# x3399.net
KiCad netlist of a schematic drawn in Altium Designer
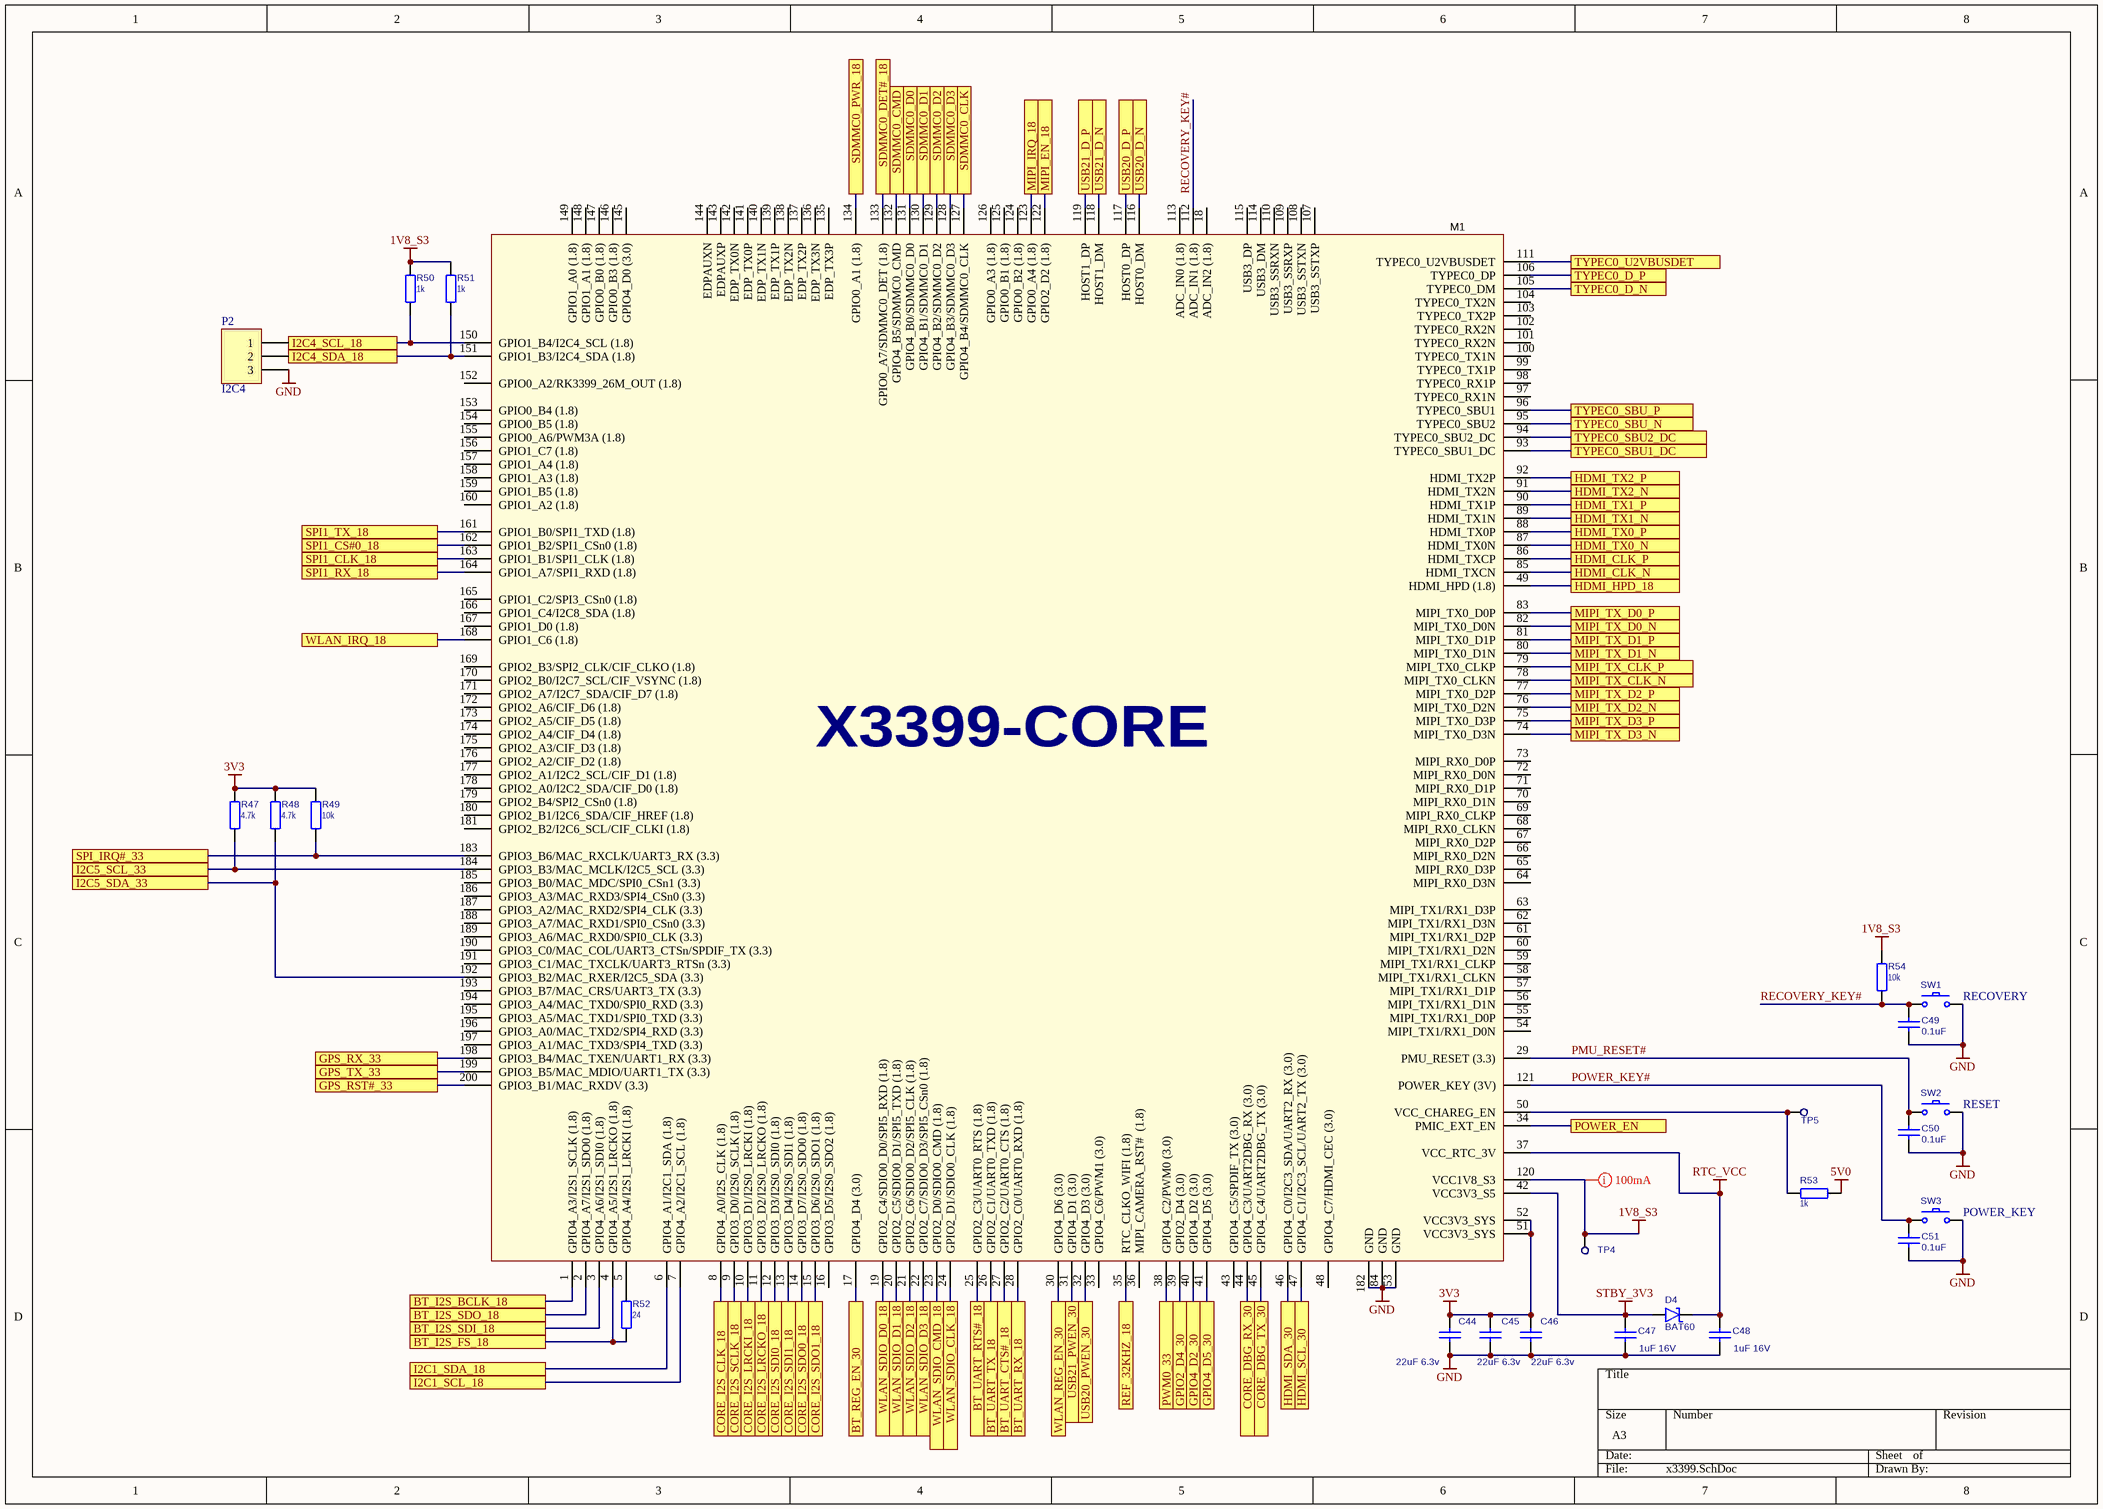
[diagram p0: x3399.SchDoc]

(export (version "E")
  (design (tool "Eeschema 10.0.6"))
  (components
    (comp (ref "C44")
      (value "22uF 6.3v")
      (footprint "C0805")
      (description "CAP_NPOL")
      (fields (field (name "Comment") "CL21A226MQQNNNE"))
      (libsource (lib "capacitors") (part "CAP_NPOL"))
    )
    (comp (ref "C45")
      (value "22uF 6.3v")
      (footprint "C0805")
      (description "CAP_NPOL")
      (fields (field (name "Comment") "CL21A226MQQNNNE"))
      (libsource (lib "capacitors") (part "CAP_NPOL"))
    )
    (comp (ref "C46")
      (value "22uF 6.3v")
      (footprint "C0805")
      (description "CAP_NPOL")
      (fields (field (name "Comment") "CL21A226MQQNNNE"))
      (libsource (lib "capacitors") (part "CAP_NPOL"))
    )
    (comp (ref "C47")
      (value "1uF 16V")
      (footprint "Capacitors:C0603")
      (description "CAP_NPOL")
      (fields (field (name "Comment") "GRM188R61H105KAALD"))
      (libsource (lib "capacitors") (part "CAP_NPOL"))
    )
    (comp (ref "C48")
      (value "1uF 16V")
      (footprint "Capacitors:C0603")
      (description "CAP_NPOL")
      (fields (field (name "Comment") "GRM188R61H105KAALD"))
      (libsource (lib "capacitors") (part "CAP_NPOL"))
    )
    (comp (ref "C49")
      (value "0.1uF")
      (footprint "Capacitors:C0603")
      (description "CAP_NPOL")
      (fields (field (name "Comment") "C1608X7R1H104K080AA"))
      (libsource (lib "capacitors") (part "CAP_NPOL"))
    )
    (comp (ref "C50")
      (value "0.1uF")
      (footprint "Capacitors:C0603")
      (description "CAP_NPOL")
      (fields (field (name "Comment") "C1608X7R1H104K080AA"))
      (libsource (lib "capacitors") (part "CAP_NPOL"))
    )
    (comp (ref "C51")
      (value "0.1uF")
      (footprint "Capacitors:C0603")
      (description "CAP_NPOL")
      (fields (field (name "Comment") "C1608X7R1H104K080AA"))
      (libsource (lib "capacitors") (part "CAP_NPOL"))
    )
    (comp (ref "D4")
      (value "BAT60")
      (footprint "SOD-323")
      (description "SHOTTKY")
      (fields (field (name "Comment") "BAT60AE6327HTSA1"))
      (libsource (lib "diodes") (part "SHOTTKY"))
    )
    (comp (ref "M1")
      (value "X3399-CORE")
      (footprint "X3399-CORE")
      (description "RK3399 Six-Core 64-bit")
      (libsource (lib "X3399-CORE") (part "X3399-CORE"))
    )
    (comp (ref "P2")
      (value "I2C4")
      (footprint "PLS-3")
      (description "Header, 3-Pin")
      (fields (field (name "PUBLISHER") "Altium Limited"))
      (libsource (lib "HDR") (part "HDR 3"))
    )
    (comp (ref "R47")
      (value "4.7k")
      (footprint "R0603")
      (description "RES")
      (libsource (lib "resistors") (part "RESISTOR"))
    )
    (comp (ref "R48")
      (value "4.7k")
      (footprint "R0603")
      (description "RES")
      (libsource (lib "resistors") (part "RESISTOR"))
    )
    (comp (ref "R49")
      (value "10k")
      (footprint "R0603")
      (description "RES")
      (libsource (lib "resistors") (part "RESISTOR"))
    )
    (comp (ref "R50")
      (value "1k")
      (footprint "R0603")
      (description "RES")
      (libsource (lib "resistors") (part "RESISTOR"))
    )
    (comp (ref "R51")
      (value "1k")
      (footprint "R0603")
      (description "RES")
      (libsource (lib "resistors") (part "RESISTOR"))
    )
    (comp (ref "R52")
      (value "24")
      (footprint "R0603")
      (description "RES")
      (libsource (lib "resistors") (part "RESISTOR"))
    )
    (comp (ref "R53")
      (value "1k")
      (footprint "R0603")
      (description "RES")
      (libsource (lib "resistors") (part "RESISTOR"))
    )
    (comp (ref "R54")
      (value "10k")
      (footprint "R0603")
      (description "RES")
      (libsource (lib "resistors") (part "RESISTOR"))
    )
    (comp (ref "SW1")
      (value "RECOVERY")
      (footprint "TACTM-34N-F")
      (description "Microswitches, DTSMB-3 series")
      (libsource (lib "SW-TACT-2PIN") (part "SW tact 2-pin"))
    )
    (comp (ref "SW2")
      (value "RESET")
      (footprint "TACTM-34N-F")
      (description "Microswitches, DTSMB-3 series")
      (libsource (lib "SW-TACT-2PIN") (part "SW tact 2-pin"))
    )
    (comp (ref "SW3")
      (value "POWER_KEY")
      (footprint "TACTM-34N-F")
      (description "Microswitches, DTSMB-3 series")
      (libsource (lib "SW-TACT-2PIN") (part "SW tact 2-pin"))
    )
    (comp (ref "TP4")
      (value "TEST-POINT")
      (footprint "PAD")
      (description "PCB terminal block")
      (libsource (lib "TestPoint") (part "TEST-POINT"))
    )
    (comp (ref "TP5")
      (value "TEST-POINT")
      (footprint "PAD")
      (description "PCB terminal block")
      (libsource (lib "TestPoint") (part "TEST-POINT"))
    )
  )
  (nets
    (net (code "1") (name "/BT_I2S_BCLK_18") (class "Default")
      (node (ref "M1") (pin "1") (pinfunction "GPIO4_A3/I2S1_SCLK_(1.8)_1") (pintype "passive"))
    )
    (net (code "2") (name "/BT_I2S_FS_18") (class "Default")
      (node (ref "M1") (pin "4") (pinfunction "GPIO4_A5/I2S1_LRCKO_(1.8)_4") (pintype "passive"))
      (node (ref "R52") (pin "2") (pinfunction "2_2") (pintype "passive"))
    )
    (net (code "3") (name "/BT_I2S_SDI_18") (class "Default")
      (node (ref "M1") (pin "3") (pinfunction "GPIO4_A6/I2S1_SDI0_(1.8)_3") (pintype "passive"))
    )
    (net (code "4") (name "/BT_I2S_SDO_18") (class "Default")
      (node (ref "M1") (pin "2") (pinfunction "GPIO4_A7/I2S1_SDO0_(1.8)_2") (pintype "passive"))
    )
    (net (code "5") (name "/BT_REG_EN_30") (class "Default")
      (node (ref "M1") (pin "17") (pinfunction "GPIO4_D4_(3.0)_17") (pintype "passive"))
    )
    (net (code "6") (name "/BT_UART_CTS#_18") (class "Default")
      (node (ref "M1") (pin "27") (pinfunction "GPIO2_C2/UART0_CTS_(1.8)_27") (pintype "passive"))
    )
    (net (code "7") (name "/BT_UART_RTS#_18") (class "Default")
      (node (ref "M1") (pin "25") (pinfunction "GPIO2_C3/UART0_RTS_(1.8)_25") (pintype "passive"))
    )
    (net (code "8") (name "/BT_UART_RX_18") (class "Default")
      (node (ref "M1") (pin "28") (pinfunction "GPIO2_C0/UART0_RXD_(1.8)_28") (pintype "passive"))
    )
    (net (code "9") (name "/BT_UART_TX_18") (class "Default")
      (node (ref "M1") (pin "26") (pinfunction "GPIO2_C1/UART0_TXD_(1.8)_26") (pintype "passive"))
    )
    (net (code "10") (name "/CORE_DBG_RX_30") (class "Default")
      (node (ref "M1") (pin "44") (pinfunction "GPIO4_C3/UART2DBG_RX_(3.0)_44") (pintype "passive"))
    )
    (net (code "11") (name "/CORE_DBG_TX_30") (class "Default")
      (node (ref "M1") (pin "45") (pinfunction "GPIO4_C4/UART2DBG_TX_(3.0)_45") (pintype "passive"))
    )
    (net (code "12") (name "/CORE_I2S_CLK_18") (class "Default")
      (node (ref "M1") (pin "8") (pinfunction "GPIO4_A0/I2S_CLK_(1.8)_8") (pintype "passive"))
    )
    (net (code "13") (name "/CORE_I2S_LRCKI_18") (class "Default")
      (node (ref "M1") (pin "10") (pinfunction "GPIO3_D1/I2S0_LRCKI_(1.8)_10") (pintype "passive"))
    )
    (net (code "14") (name "/CORE_I2S_LRCKO_18") (class "Default")
      (node (ref "M1") (pin "11") (pinfunction "GPIO3_D2/I2S0_LRCKO_(1.8)_11") (pintype "passive"))
    )
    (net (code "15") (name "/CORE_I2S_SCLK_18") (class "Default")
      (node (ref "M1") (pin "9") (pinfunction "GPIO3_D0/I2S0_SCLK_(1.8)_9") (pintype "passive"))
    )
    (net (code "16") (name "/CORE_I2S_SDI0_18") (class "Default")
      (node (ref "M1") (pin "12") (pinfunction "GPIO3_D3/I2S0_SDI0_(1.8)_12") (pintype "passive"))
    )
    (net (code "17") (name "/CORE_I2S_SDI1_18") (class "Default")
      (node (ref "M1") (pin "13") (pinfunction "GPIO3_D4/I2S0_SDI1_(1.8)_13") (pintype "passive"))
    )
    (net (code "18") (name "/CORE_I2S_SDO0_18") (class "Default")
      (node (ref "M1") (pin "14") (pinfunction "GPIO3_D7/I2S0_SDO0_(1.8)_14") (pintype "passive"))
    )
    (net (code "19") (name "/CORE_I2S_SDO1_18") (class "Default")
      (node (ref "M1") (pin "15") (pinfunction "GPIO3_D6/I2S0_SDO1_(1.8)_15") (pintype "passive"))
    )
    (net (code "20") (name "/GPIO2_D4_30") (class "Default")
      (node (ref "M1") (pin "39") (pinfunction "GPIO2_D4_(3.0)_39") (pintype "passive"))
    )
    (net (code "21") (name "/GPIO4_D2_30") (class "Default")
      (node (ref "M1") (pin "40") (pinfunction "GPIO4_D2_(3.0)_40") (pintype "passive"))
    )
    (net (code "22") (name "/GPIO4_D5_30") (class "Default")
      (node (ref "M1") (pin "41") (pinfunction "GPIO4_D5_(3.0)_41") (pintype "passive"))
    )
    (net (code "23") (name "/GPS_RST#_33") (class "Default")
      (node (ref "M1") (pin "200") (pinfunction "GPIO3_B1/MAC_RXDV_(3.3)_200") (pintype "passive"))
    )
    (net (code "24") (name "/GPS_RX_33") (class "Default")
      (node (ref "M1") (pin "198") (pinfunction "GPIO3_B4/MAC_TXEN/UART1_RX_(3.3)_198") (pintype "passive"))
    )
    (net (code "25") (name "/GPS_TX_33") (class "Default")
      (node (ref "M1") (pin "199") (pinfunction "GPIO3_B5/MAC_MDIO/UART1_TX_(3.3)_199") (pintype "passive"))
    )
    (net (code "26") (name "/HDMI_CLK_N") (class "Default")
      (node (ref "M1") (pin "85") (pinfunction "HDMI_TXCN_85") (pintype "passive"))
    )
    (net (code "27") (name "/HDMI_CLK_P") (class "Default")
      (node (ref "M1") (pin "86") (pinfunction "HDMI_TXCP_86") (pintype "passive"))
    )
    (net (code "28") (name "/HDMI_HPD_18") (class "Default")
      (node (ref "M1") (pin "49") (pinfunction "HDMI_HPD_(1.8)_49") (pintype "passive"))
    )
    (net (code "29") (name "/HDMI_SCL_30") (class "Default")
      (node (ref "M1") (pin "47") (pinfunction "GPIO4_C1/I2C3_SCL/UART2_TX_(3.0)_47") (pintype "passive"))
    )
    (net (code "30") (name "/HDMI_SDA_30") (class "Default")
      (node (ref "M1") (pin "46") (pinfunction "GPIO4_C0/I2C3_SDA/UART2_RX_(3.0)_46") (pintype "passive"))
    )
    (net (code "31") (name "/HDMI_TX0_N") (class "Default")
      (node (ref "M1") (pin "87") (pinfunction "HDMI_TX0N_87") (pintype "passive"))
    )
    (net (code "32") (name "/HDMI_TX0_P") (class "Default")
      (node (ref "M1") (pin "88") (pinfunction "HDMI_TX0P_88") (pintype "passive"))
    )
    (net (code "33") (name "/HDMI_TX1_N") (class "Default")
      (node (ref "M1") (pin "89") (pinfunction "HDMI_TX1N_89") (pintype "passive"))
    )
    (net (code "34") (name "/HDMI_TX1_P") (class "Default")
      (node (ref "M1") (pin "90") (pinfunction "HDMI_TX1P_90") (pintype "passive"))
    )
    (net (code "35") (name "/HDMI_TX2_N") (class "Default")
      (node (ref "M1") (pin "91") (pinfunction "HDMI_TX2N_91") (pintype "passive"))
    )
    (net (code "36") (name "/HDMI_TX2_P") (class "Default")
      (node (ref "M1") (pin "92") (pinfunction "HDMI_TX2P_92") (pintype "passive"))
    )
    (net (code "37") (name "/I2C1_SCL_18") (class "Default")
      (node (ref "M1") (pin "7") (pinfunction "GPIO4_A2/I2C1_SCL_(1.8)_7") (pintype "passive"))
    )
    (net (code "38") (name "/I2C1_SDA_18") (class "Default")
      (node (ref "M1") (pin "6") (pinfunction "GPIO4_A1/I2C1_SDA_(1.8)_6") (pintype "passive"))
    )
    (net (code "39") (name "/I2C4_SCL_18") (class "Default")
      (node (ref "M1") (pin "150") (pinfunction "GPIO1_B4/I2C4_SCL_(1.8)_150") (pintype "passive"))
      (node (ref "P2") (pin "1") (pinfunction "1_1") (pintype "passive"))
      (node (ref "R50") (pin "1") (pinfunction "1_1") (pintype "passive"))
    )
    (net (code "40") (name "/I2C4_SDA_18") (class "Default")
      (node (ref "M1") (pin "151") (pinfunction "GPIO1_B3/I2C4_SDA_(1.8)_151") (pintype "passive"))
      (node (ref "P2") (pin "2") (pinfunction "2_2") (pintype "passive"))
      (node (ref "R51") (pin "2") (pinfunction "2_2") (pintype "passive"))
    )
    (net (code "41") (name "/I2C5_SCL_33") (class "Default")
      (node (ref "M1") (pin "184") (pinfunction "GPIO3_B3/MAC_MCLK/I2C5_SCL_(3.3)_184") (pintype "passive"))
      (node (ref "R47") (pin "1") (pinfunction "1_1") (pintype "passive"))
    )
    (net (code "42") (name "/I2C5_SDA_33") (class "Default")
      (node (ref "M1") (pin "192") (pinfunction "GPIO3_B2/MAC_RXER/I2C5_SDA_(3.3)_192") (pintype "passive"))
      (node (ref "R48") (pin "2") (pinfunction "2_2") (pintype "passive"))
    )
    (net (code "43") (name "/MIPI_EN_18") (class "Default")
      (node (ref "M1") (pin "122") (pinfunction "GPIO2_D2_(1.8)_122") (pintype "passive"))
    )
    (net (code "44") (name "/MIPI_IRQ_18") (class "Default")
      (node (ref "M1") (pin "123") (pinfunction "GPIO0_A4_(1.8)_123") (pintype "passive"))
    )
    (net (code "45") (name "/MIPI_TX_CLK_N") (class "Default")
      (node (ref "M1") (pin "78") (pinfunction "MIPI_TX0_CLKN_78") (pintype "passive"))
    )
    (net (code "46") (name "/MIPI_TX_CLK_P") (class "Default")
      (node (ref "M1") (pin "79") (pinfunction "MIPI_TX0_CLKP_79") (pintype "passive"))
    )
    (net (code "47") (name "/MIPI_TX_D0_N") (class "Default")
      (node (ref "M1") (pin "82") (pinfunction "MIPI_TX0_D0N_82") (pintype "passive"))
    )
    (net (code "48") (name "/MIPI_TX_D0_P") (class "Default")
      (node (ref "M1") (pin "83") (pinfunction "MIPI_TX0_D0P_83") (pintype "passive"))
    )
    (net (code "49") (name "/MIPI_TX_D1_N") (class "Default")
      (node (ref "M1") (pin "80") (pinfunction "MIPI_TX0_D1N_80") (pintype "passive"))
    )
    (net (code "50") (name "/MIPI_TX_D1_P") (class "Default")
      (node (ref "M1") (pin "81") (pinfunction "MIPI_TX0_D1P_81") (pintype "passive"))
    )
    (net (code "51") (name "/MIPI_TX_D2_N") (class "Default")
      (node (ref "M1") (pin "76") (pinfunction "MIPI_TX0_D2N_76") (pintype "passive"))
    )
    (net (code "52") (name "/MIPI_TX_D2_P") (class "Default")
      (node (ref "M1") (pin "77") (pinfunction "MIPI_TX0_D2P_77") (pintype "passive"))
    )
    (net (code "53") (name "/MIPI_TX_D3_N") (class "Default")
      (node (ref "M1") (pin "74") (pinfunction "MIPI_TX0_D3N_74") (pintype "passive"))
    )
    (net (code "54") (name "/MIPI_TX_D3_P") (class "Default")
      (node (ref "M1") (pin "75") (pinfunction "MIPI_TX0_D3P_75") (pintype "passive"))
    )
    (net (code "55") (name "/PMU_RESET#") (class "Default")
      (node (ref "C50") (pin "1") (pinfunction "1_1") (pintype "passive"))
      (node (ref "M1") (pin "29") (pinfunction "PMU_RESET_(3.3)_29") (pintype "passive"))
      (node (ref "SW2") (pin "1") (pintype "passive"))
    )
    (net (code "56") (name "/POWER_EN") (class "Default")
      (node (ref "M1") (pin "34") (pinfunction "PMIC_EXT_EN_34") (pintype "passive"))
    )
    (net (code "57") (name "/POWER_KEY#") (class "Default")
      (node (ref "C51") (pin "1") (pinfunction "1_1") (pintype "passive"))
      (node (ref "M1") (pin "121") (pinfunction "POWER_KEY_(3V)_121") (pintype "passive"))
      (node (ref "SW3") (pin "1") (pintype "passive"))
    )
    (net (code "58") (name "/PWM0_33") (class "Default")
      (node (ref "M1") (pin "38") (pinfunction "GPIO4_C2/PWM0_(3.0)_38") (pintype "passive"))
    )
    (net (code "59") (name "/RECOVERY_KEY#") (class "Default")
      (node (ref "C49") (pin "1") (pinfunction "1_1") (pintype "passive"))
      (node (ref "M1") (pin "112") (pinfunction "ADC_IN1_(1.8)_112") (pintype "passive"))
      (node (ref "R54") (pin "1") (pinfunction "1_1") (pintype "passive"))
      (node (ref "SW1") (pin "1") (pintype "passive"))
    )
    (net (code "60") (name "/REF_32KHZ_18") (class "Default")
      (node (ref "M1") (pin "35") (pinfunction "RTC_CLKO_WIFI_(1.8)_35") (pintype "passive"))
    )
    (net (code "61") (name "/SDMMC0_CLK") (class "Default")
      (node (ref "M1") (pin "127") (pinfunction "GPIO4_B4/SDMMC0_CLK_127") (pintype "passive"))
    )
    (net (code "62") (name "/SDMMC0_CMD") (class "Default")
      (node (ref "M1") (pin "132") (pinfunction "GPIO4_B5/SDMMC0_CMD_132") (pintype "passive"))
    )
    (net (code "63") (name "/SDMMC0_D0") (class "Default")
      (node (ref "M1") (pin "131") (pinfunction "GPIO4_B0/SDMMC0_D0_131") (pintype "passive"))
    )
    (net (code "64") (name "/SDMMC0_D1") (class "Default")
      (node (ref "M1") (pin "130") (pinfunction "GPIO4_B1/SDMMC0_D1_130") (pintype "passive"))
    )
    (net (code "65") (name "/SDMMC0_D2") (class "Default")
      (node (ref "M1") (pin "129") (pinfunction "GPIO4_B2/SDMMC0_D2_129") (pintype "passive"))
    )
    (net (code "66") (name "/SDMMC0_D3") (class "Default")
      (node (ref "M1") (pin "128") (pinfunction "GPIO4_B3/SDMMC0_D3_128") (pintype "passive"))
    )
    (net (code "67") (name "/SDMMC0_DET#_18") (class "Default")
      (node (ref "M1") (pin "133") (pinfunction "GPIO0_A7/SDMMC0_DET_(1.8)_133") (pintype "passive"))
    )
    (net (code "68") (name "/SDMMC0_PWR_18") (class "Default")
      (node (ref "M1") (pin "134") (pinfunction "GPIO0_A1_(1.8)_134") (pintype "passive"))
    )
    (net (code "69") (name "/SPI1_CLK_18") (class "Default")
      (node (ref "M1") (pin "163") (pinfunction "GPIO1_B1/SPI1_CLK_(1.8)_163") (pintype "passive"))
    )
    (net (code "70") (name "/SPI1_CS#0_18") (class "Default")
      (node (ref "M1") (pin "162") (pinfunction "GPIO1_B2/SPI1_CSn0_(1.8)_162") (pintype "passive"))
    )
    (net (code "71") (name "/SPI1_RX_18") (class "Default")
      (node (ref "M1") (pin "164") (pinfunction "GPIO1_A7/SPI1_RXD_(1.8)_164") (pintype "passive"))
    )
    (net (code "72") (name "/SPI1_TX_18") (class "Default")
      (node (ref "M1") (pin "161") (pinfunction "GPIO1_B0/SPI1_TXD_(1.8)_161") (pintype "passive"))
    )
    (net (code "73") (name "/SPI_IRQ#_33") (class "Default")
      (node (ref "M1") (pin "183") (pinfunction "GPIO3_B6/MAC_RXCLK/UART3_RX_(3.3)_183") (pintype "passive"))
      (node (ref "R49") (pin "2") (pinfunction "2_2") (pintype "passive"))
    )
    (net (code "74") (name "/TYPEC0_D_N") (class "Default")
      (node (ref "M1") (pin "105") (pinfunction "TYPEC0_DM_105") (pintype "passive"))
    )
    (net (code "75") (name "/TYPEC0_D_P") (class "Default")
      (node (ref "M1") (pin "106") (pinfunction "TYPEC0_DP_106") (pintype "passive"))
    )
    (net (code "76") (name "/TYPEC0_SBU1_DC") (class "Default")
      (node (ref "M1") (pin "93") (pinfunction "TYPEC0_SBU1_DC_93") (pintype "passive"))
    )
    (net (code "77") (name "/TYPEC0_SBU2_DC") (class "Default")
      (node (ref "M1") (pin "94") (pinfunction "TYPEC0_SBU2_DC_94") (pintype "passive"))
    )
    (net (code "78") (name "/TYPEC0_SBU_N") (class "Default")
      (node (ref "M1") (pin "95") (pinfunction "TYPEC0_SBU2_95") (pintype "passive"))
    )
    (net (code "79") (name "/TYPEC0_SBU_P") (class "Default")
      (node (ref "M1") (pin "96") (pinfunction "TYPEC0_SBU1_96") (pintype "passive"))
    )
    (net (code "80") (name "/TYPEC0_U2VBUSDET") (class "Default")
      (node (ref "M1") (pin "111") (pinfunction "TYPEC0_U2VBUSDET_111") (pintype "passive"))
    )
    (net (code "81") (name "/USB20_D_N") (class "Default")
      (node (ref "M1") (pin "116") (pinfunction "HOST0_DM_116") (pintype "passive"))
    )
    (net (code "82") (name "/USB20_D_P") (class "Default")
      (node (ref "M1") (pin "117") (pinfunction "HOST0_DP_117") (pintype "passive"))
    )
    (net (code "83") (name "/USB20_PWEN_30") (class "Default")
      (node (ref "M1") (pin "32") (pinfunction "GPIO4_D3_(3.0)_32") (pintype "passive"))
    )
    (net (code "84") (name "/USB21_D_N") (class "Default")
      (node (ref "M1") (pin "118") (pinfunction "HOST1_DM_118") (pintype "passive"))
    )
    (net (code "85") (name "/USB21_D_P") (class "Default")
      (node (ref "M1") (pin "119") (pinfunction "HOST1_DP_119") (pintype "passive"))
    )
    (net (code "86") (name "/USB21_PWEN_30") (class "Default")
      (node (ref "M1") (pin "31") (pinfunction "GPIO4_D1_(3.0)_31") (pintype "passive"))
    )
    (net (code "87") (name "/WLAN_IRQ_18") (class "Default")
      (node (ref "M1") (pin "168") (pinfunction "GPIO1_C6_(1.8)_168") (pintype "passive"))
    )
    (net (code "88") (name "/WLAN_REG_EN_30") (class "Default")
      (node (ref "M1") (pin "30") (pinfunction "GPIO4_D6_(3.0)_30") (pintype "passive"))
    )
    (net (code "89") (name "/WLAN_SDIO_CLK_18") (class "Default")
      (node (ref "M1") (pin "24") (pinfunction "GPIO2_D1/SDIO0_CLK_(1.8)_24") (pintype "passive"))
    )
    (net (code "90") (name "/WLAN_SDIO_CMD_18") (class "Default")
      (node (ref "M1") (pin "23") (pinfunction "GPIO2_D0/SDIO0_CMD_(1.8)_23") (pintype "passive"))
    )
    (net (code "91") (name "/WLAN_SDIO_D0_18") (class "Default")
      (node (ref "M1") (pin "19") (pinfunction "GPIO2_C4/SDIO0_D0/SPI5_RXD_(1.8)_19") (pintype "passive"))
    )
    (net (code "92") (name "/WLAN_SDIO_D1_18") (class "Default")
      (node (ref "M1") (pin "20") (pinfunction "GPIO2_C5/SDIO0_D1/SPI5_TXD_(1.8)_20") (pintype "passive"))
    )
    (net (code "93") (name "/WLAN_SDIO_D2_18") (class "Default")
      (node (ref "M1") (pin "21") (pinfunction "GPIO2_C6/SDIO0_D2/SPI5_CLK_(1.8)_21") (pintype "passive"))
    )
    (net (code "94") (name "/WLAN_SDIO_D3_18") (class "Default")
      (node (ref "M1") (pin "22") (pinfunction "GPIO2_C7/SDIO0_D3/SPI5_CSn0_(1.8)_22") (pintype "passive"))
    )
    (net (code "95") (name "1V8_S3") (class "Default")
      (node (ref "M1") (pin "120") (pinfunction "VCC1V8_S3_120") (pintype "passive"))
      (node (ref "R50") (pin "2") (pinfunction "2_2") (pintype "passive"))
      (node (ref "R51") (pin "1") (pinfunction "1_1") (pintype "passive"))
      (node (ref "R54") (pin "2") (pinfunction "2_2") (pintype "passive"))
      (node (ref "TP4") (pin "1") (pinfunction "1_1") (pintype "passive"))
    )
    (net (code "96") (name "3V3") (class "Default")
      (node (ref "C44") (pin "1") (pinfunction "1_1") (pintype "passive"))
      (node (ref "C45") (pin "1") (pinfunction "1_1") (pintype "passive"))
      (node (ref "C46") (pin "1") (pinfunction "1_1") (pintype "passive"))
      (node (ref "M1") (pin "51") (pinfunction "VCC3V3_SYS_51") (pintype "passive"))
      (node (ref "M1") (pin "52") (pinfunction "VCC3V3_SYS_52") (pintype "passive"))
      (node (ref "R47") (pin "2") (pinfunction "2_2") (pintype "passive"))
      (node (ref "R48") (pin "1") (pinfunction "1_1") (pintype "passive"))
      (node (ref "R49") (pin "1") (pinfunction "1_1") (pintype "passive"))
    )
    (net (code "97") (name "5V0") (class "Default")
      (node (ref "R53") (pin "1") (pinfunction "1_1") (pintype "passive"))
    )
    (net (code "98") (name "GND") (class "Default")
      (node (ref "C44") (pin "2") (pinfunction "2_2") (pintype "passive"))
      (node (ref "C45") (pin "2") (pinfunction "2_2") (pintype "passive"))
      (node (ref "C46") (pin "2") (pinfunction "2_2") (pintype "passive"))
      (node (ref "C47") (pin "1") (pinfunction "1_1") (pintype "passive"))
      (node (ref "C48") (pin "1") (pinfunction "1_1") (pintype "passive"))
      (node (ref "C49") (pin "2") (pinfunction "2_2") (pintype "passive"))
      (node (ref "C50") (pin "2") (pinfunction "2_2") (pintype "passive"))
      (node (ref "C51") (pin "2") (pinfunction "2_2") (pintype "passive"))
      (node (ref "M1") (pin "182") (pinfunction "GND_182") (pintype "passive"))
      (node (ref "M1") (pin "53") (pinfunction "GND_53") (pintype "passive"))
      (node (ref "M1") (pin "84") (pinfunction "GND_84") (pintype "passive"))
      (node (ref "P2") (pin "3") (pinfunction "3_3") (pintype "passive"))
      (node (ref "SW1") (pin "2") (pintype "passive"))
      (node (ref "SW2") (pin "2") (pintype "passive"))
      (node (ref "SW3") (pin "2") (pintype "passive"))
    )
    (net (code "99") (name "Net-(M1-GPIO4_A4{slash}I2S1_LRCKI_(1.8))") (class "Default")
      (node (ref "M1") (pin "5") (pinfunction "GPIO4_A4/I2S1_LRCKI_(1.8)_5") (pintype "passive"))
      (node (ref "R52") (pin "1") (pinfunction "1_1") (pintype "passive"))
    )
    (net (code "100") (name "Net-(M1-VCC_CHAREG_EN)") (class "Default")
      (node (ref "M1") (pin "50") (pinfunction "VCC_CHAREG_EN_50") (pintype "passive"))
      (node (ref "R53") (pin "2") (pinfunction "2_2") (pintype "passive"))
      (node (ref "TP5") (pin "1") (pinfunction "1_1") (pintype "passive"))
    )
    (net (code "101") (name "RTC_VCC") (class "Default")
      (node (ref "C48") (pin "2") (pinfunction "2_2") (pintype "passive"))
      (node (ref "D4") (pin "2") (pinfunction "K_2") (pintype "passive"))
      (node (ref "M1") (pin "37") (pinfunction "VCC_RTC_3V_37") (pintype "passive"))
    )
    (net (code "102") (name "STBY_3V3") (class "Default")
      (node (ref "C47") (pin "2") (pinfunction "2_2") (pintype "passive"))
      (node (ref "D4") (pin "1") (pinfunction "A_1") (pintype "passive"))
      (node (ref "M1") (pin "42") (pinfunction "VCC3V3_S5_42") (pintype "passive"))
    )
    (net (code "103") (name "unconnected-(M1-ADC_IN0_(1.8)-Pad113)") (class "Default")
      (node (ref "M1") (pin "113") (pinfunction "ADC_IN0_(1.8)_113") (pintype "passive"))
    )
    (net (code "104") (name "unconnected-(M1-ADC_IN2_(1.8)-Pad18)") (class "Default")
      (node (ref "M1") (pin "18") (pinfunction "ADC_IN2_(1.8)_18") (pintype "passive"))
    )
    (net (code "105") (name "unconnected-(M1-EDPAUXN-Pad144)") (class "Default")
      (node (ref "M1") (pin "144") (pinfunction "EDPAUXN_144") (pintype "passive"))
    )
    (net (code "106") (name "unconnected-(M1-EDPAUXP-Pad143)") (class "Default")
      (node (ref "M1") (pin "143") (pinfunction "EDPAUXP_143") (pintype "passive"))
    )
    (net (code "107") (name "unconnected-(M1-EDP_TX0N-Pad142)") (class "Default")
      (node (ref "M1") (pin "142") (pinfunction "EDP_TX0N_142") (pintype "passive"))
    )
    (net (code "108") (name "unconnected-(M1-EDP_TX0P-Pad141)") (class "Default")
      (node (ref "M1") (pin "141") (pinfunction "EDP_TX0P_141") (pintype "passive"))
    )
    (net (code "109") (name "unconnected-(M1-EDP_TX1N-Pad140)") (class "Default")
      (node (ref "M1") (pin "140") (pinfunction "EDP_TX1N_140") (pintype "passive"))
    )
    (net (code "110") (name "unconnected-(M1-EDP_TX1P-Pad139)") (class "Default")
      (node (ref "M1") (pin "139") (pinfunction "EDP_TX1P_139") (pintype "passive"))
    )
    (net (code "111") (name "unconnected-(M1-EDP_TX2N-Pad138)") (class "Default")
      (node (ref "M1") (pin "138") (pinfunction "EDP_TX2N_138") (pintype "passive"))
    )
    (net (code "112") (name "unconnected-(M1-EDP_TX2P-Pad137)") (class "Default")
      (node (ref "M1") (pin "137") (pinfunction "EDP_TX2P_137") (pintype "passive"))
    )
    (net (code "113") (name "unconnected-(M1-EDP_TX3N-Pad136)") (class "Default")
      (node (ref "M1") (pin "136") (pinfunction "EDP_TX3N_136") (pintype "passive"))
    )
    (net (code "114") (name "unconnected-(M1-EDP_TX3P-Pad135)") (class "Default")
      (node (ref "M1") (pin "135") (pinfunction "EDP_TX3P_135") (pintype "passive"))
    )
    (net (code "115") (name "unconnected-(M1-GPIO0_A2{slash}RK3399_26M_OUT_(1.8)-Pad152)") (class "Default")
      (node (ref "M1") (pin "152") (pinfunction "GPIO0_A2/RK3399_26M_OUT_(1.8)_152") (pintype "passive"))
    )
    (net (code "116") (name "unconnected-(M1-GPIO0_A3_(1.8)-Pad126)") (class "Default")
      (node (ref "M1") (pin "126") (pinfunction "GPIO0_A3_(1.8)_126") (pintype "passive"))
    )
    (net (code "117") (name "unconnected-(M1-GPIO0_A6{slash}PWM3A_(1.8)-Pad155)") (class "Default")
      (node (ref "M1") (pin "155") (pinfunction "GPIO0_A6/PWM3A_(1.8)_155") (pintype "passive"))
    )
    (net (code "118") (name "unconnected-(M1-GPIO0_B0_(1.8)-Pad147)") (class "Default")
      (node (ref "M1") (pin "147") (pinfunction "GPIO0_B0_(1.8)_147") (pintype "passive"))
    )
    (net (code "119") (name "unconnected-(M1-GPIO0_B1_(1.8)-Pad125)") (class "Default")
      (node (ref "M1") (pin "125") (pinfunction "GPIO0_B1_(1.8)_125") (pintype "passive"))
    )
    (net (code "120") (name "unconnected-(M1-GPIO0_B2_(1.8)-Pad124)") (class "Default")
      (node (ref "M1") (pin "124") (pinfunction "GPIO0_B2_(1.8)_124") (pintype "passive"))
    )
    (net (code "121") (name "unconnected-(M1-GPIO0_B3_(1.8)-Pad146)") (class "Default")
      (node (ref "M1") (pin "146") (pinfunction "GPIO0_B3_(1.8)_146") (pintype "passive"))
    )
    (net (code "122") (name "unconnected-(M1-GPIO0_B4_(1.8)-Pad153)") (class "Default")
      (node (ref "M1") (pin "153") (pinfunction "GPIO0_B4_(1.8)_153") (pintype "passive"))
    )
    (net (code "123") (name "unconnected-(M1-GPIO0_B5_(1.8)-Pad154)") (class "Default")
      (node (ref "M1") (pin "154") (pinfunction "GPIO0_B5_(1.8)_154") (pintype "passive"))
    )
    (net (code "124") (name "unconnected-(M1-GPIO1_A0_(1.8)-Pad149)") (class "Default")
      (node (ref "M1") (pin "149") (pinfunction "GPIO1_A0_(1.8)_149") (pintype "passive"))
    )
    (net (code "125") (name "unconnected-(M1-GPIO1_A1_(1.8)-Pad148)") (class "Default")
      (node (ref "M1") (pin "148") (pinfunction "GPIO1_A1_(1.8)_148") (pintype "passive"))
    )
    (net (code "126") (name "unconnected-(M1-GPIO1_A2_(1.8)-Pad160)") (class "Default")
      (node (ref "M1") (pin "160") (pinfunction "GPIO1_A2_(1.8)_160") (pintype "passive"))
    )
    (net (code "127") (name "unconnected-(M1-GPIO1_A3_(1.8)-Pad158)") (class "Default")
      (node (ref "M1") (pin "158") (pinfunction "GPIO1_A3_(1.8)_158") (pintype "passive"))
    )
    (net (code "128") (name "unconnected-(M1-GPIO1_A4_(1.8)-Pad157)") (class "Default")
      (node (ref "M1") (pin "157") (pinfunction "GPIO1_A4_(1.8)_157") (pintype "passive"))
    )
    (net (code "129") (name "unconnected-(M1-GPIO1_B5_(1.8)-Pad159)") (class "Default")
      (node (ref "M1") (pin "159") (pinfunction "GPIO1_B5_(1.8)_159") (pintype "passive"))
    )
    (net (code "130") (name "unconnected-(M1-GPIO1_C2{slash}SPI3_CSn0_(1.8)-Pad165)") (class "Default")
      (node (ref "M1") (pin "165") (pinfunction "GPIO1_C2/SPI3_CSn0_(1.8)_165") (pintype "passive"))
    )
    (net (code "131") (name "unconnected-(M1-GPIO1_C4{slash}I2C8_SDA_(1.8)-Pad166)") (class "Default")
      (node (ref "M1") (pin "166") (pinfunction "GPIO1_C4/I2C8_SDA_(1.8)_166") (pintype "passive"))
    )
    (net (code "132") (name "unconnected-(M1-GPIO1_C7_(1.8)-Pad156)") (class "Default")
      (node (ref "M1") (pin "156") (pinfunction "GPIO1_C7_(1.8)_156") (pintype "passive"))
    )
    (net (code "133") (name "unconnected-(M1-GPIO1_D0_(1.8)-Pad167)") (class "Default")
      (node (ref "M1") (pin "167") (pinfunction "GPIO1_D0_(1.8)_167") (pintype "passive"))
    )
    (net (code "134") (name "unconnected-(M1-GPIO2_A0{slash}I2C2_SDA{slash}CIF_D0_(1.8)-Pad178)") (class "Default")
      (node (ref "M1") (pin "178") (pinfunction "GPIO2_A0/I2C2_SDA/CIF_D0_(1.8)_178") (pintype "passive"))
    )
    (net (code "135") (name "unconnected-(M1-GPIO2_A1{slash}I2C2_SCL{slash}CIF_D1_(1.8)-Pad177)") (class "Default")
      (node (ref "M1") (pin "177") (pinfunction "GPIO2_A1/I2C2_SCL/CIF_D1_(1.8)_177") (pintype "passive"))
    )
    (net (code "136") (name "unconnected-(M1-GPIO2_A2{slash}CIF_D2_(1.8)-Pad176)") (class "Default")
      (node (ref "M1") (pin "176") (pinfunction "GPIO2_A2/CIF_D2_(1.8)_176") (pintype "passive"))
    )
    (net (code "137") (name "unconnected-(M1-GPIO2_A3{slash}CIF_D3_(1.8)-Pad175)") (class "Default")
      (node (ref "M1") (pin "175") (pinfunction "GPIO2_A3/CIF_D3_(1.8)_175") (pintype "passive"))
    )
    (net (code "138") (name "unconnected-(M1-GPIO2_A4{slash}CIF_D4_(1.8)-Pad174)") (class "Default")
      (node (ref "M1") (pin "174") (pinfunction "GPIO2_A4/CIF_D4_(1.8)_174") (pintype "passive"))
    )
    (net (code "139") (name "unconnected-(M1-GPIO2_A5{slash}CIF_D5_(1.8)-Pad173)") (class "Default")
      (node (ref "M1") (pin "173") (pinfunction "GPIO2_A5/CIF_D5_(1.8)_173") (pintype "passive"))
    )
    (net (code "140") (name "unconnected-(M1-GPIO2_A6{slash}CIF_D6_(1.8)-Pad172)") (class "Default")
      (node (ref "M1") (pin "172") (pinfunction "GPIO2_A6/CIF_D6_(1.8)_172") (pintype "passive"))
    )
    (net (code "141") (name "unconnected-(M1-GPIO2_A7{slash}I2C7_SDA{slash}CIF_D7_(1.8)-Pad171)") (class "Default")
      (node (ref "M1") (pin "171") (pinfunction "GPIO2_A7/I2C7_SDA/CIF_D7_(1.8)_171") (pintype "passive"))
    )
    (net (code "142") (name "unconnected-(M1-GPIO2_B0{slash}I2C7_SCL{slash}CIF_VSYNC_(1.8)-Pad170)") (class "Default")
      (node (ref "M1") (pin "170") (pinfunction "GPIO2_B0/I2C7_SCL/CIF_VSYNC_(1.8)_170") (pintype "passive"))
    )
    (net (code "143") (name "unconnected-(M1-GPIO2_B1{slash}I2C6_SDA{slash}CIF_HREF_(1.8)-Pad180)") (class "Default")
      (node (ref "M1") (pin "180") (pinfunction "GPIO2_B1/I2C6_SDA/CIF_HREF_(1.8)_180") (pintype "passive"))
    )
    (net (code "144") (name "unconnected-(M1-GPIO2_B2{slash}I2C6_SCL{slash}CIF_CLKI_(1.8)-Pad181)") (class "Default")
      (node (ref "M1") (pin "181") (pinfunction "GPIO2_B2/I2C6_SCL/CIF_CLKI_(1.8)_181") (pintype "passive"))
    )
    (net (code "145") (name "unconnected-(M1-GPIO2_B3{slash}SPI2_CLK{slash}CIF_CLKO_(1.8)-Pad169)") (class "Default")
      (node (ref "M1") (pin "169") (pinfunction "GPIO2_B3/SPI2_CLK/CIF_CLKO_(1.8)_169") (pintype "passive"))
    )
    (net (code "146") (name "unconnected-(M1-GPIO2_B4{slash}SPI2_CSn0_(1.8)-Pad179)") (class "Default")
      (node (ref "M1") (pin "179") (pinfunction "GPIO2_B4/SPI2_CSn0_(1.8)_179") (pintype "passive"))
    )
    (net (code "147") (name "unconnected-(M1-GPIO3_A0{slash}MAC_TXD2{slash}SPI4_RXD_(3.3)-Pad196)") (class "Default")
      (node (ref "M1") (pin "196") (pinfunction "GPIO3_A0/MAC_TXD2/SPI4_RXD_(3.3)_196") (pintype "passive"))
    )
    (net (code "148") (name "unconnected-(M1-GPIO3_A1{slash}MAC_TXD3{slash}SPI4_TXD_(3.3)-Pad197)") (class "Default")
      (node (ref "M1") (pin "197") (pinfunction "GPIO3_A1/MAC_TXD3/SPI4_TXD_(3.3)_197") (pintype "passive"))
    )
    (net (code "149") (name "unconnected-(M1-GPIO3_A2{slash}MAC_RXD2{slash}SPI4_CLK_(3.3)-Pad187)") (class "Default")
      (node (ref "M1") (pin "187") (pinfunction "GPIO3_A2/MAC_RXD2/SPI4_CLK_(3.3)_187") (pintype "passive"))
    )
    (net (code "150") (name "unconnected-(M1-GPIO3_A3{slash}MAC_RXD3{slash}SPI4_CSn0_(3.3)-Pad186)") (class "Default")
      (node (ref "M1") (pin "186") (pinfunction "GPIO3_A3/MAC_RXD3/SPI4_CSn0_(3.3)_186") (pintype "passive"))
    )
    (net (code "151") (name "unconnected-(M1-GPIO3_A4{slash}MAC_TXD0{slash}SPI0_RXD_(3.3)-Pad194)") (class "Default")
      (node (ref "M1") (pin "194") (pinfunction "GPIO3_A4/MAC_TXD0/SPI0_RXD_(3.3)_194") (pintype "passive"))
    )
    (net (code "152") (name "unconnected-(M1-GPIO3_A5{slash}MAC_TXD1{slash}SPI0_TXD_(3.3)-Pad195)") (class "Default")
      (node (ref "M1") (pin "195") (pinfunction "GPIO3_A5/MAC_TXD1/SPI0_TXD_(3.3)_195") (pintype "passive"))
    )
    (net (code "153") (name "unconnected-(M1-GPIO3_A6{slash}MAC_RXD0{slash}SPI0_CLK_(3.3)-Pad189)") (class "Default")
      (node (ref "M1") (pin "189") (pinfunction "GPIO3_A6/MAC_RXD0/SPI0_CLK_(3.3)_189") (pintype "passive"))
    )
    (net (code "154") (name "unconnected-(M1-GPIO3_A7{slash}MAC_RXD1{slash}SPI0_CSn0_(3.3)-Pad188)") (class "Default")
      (node (ref "M1") (pin "188") (pinfunction "GPIO3_A7/MAC_RXD1/SPI0_CSn0_(3.3)_188") (pintype "passive"))
    )
    (net (code "155") (name "unconnected-(M1-GPIO3_B0{slash}MAC_MDC{slash}SPI0_CSn1_(3.3)-Pad185)") (class "Default")
      (node (ref "M1") (pin "185") (pinfunction "GPIO3_B0/MAC_MDC/SPI0_CSn1_(3.3)_185") (pintype "passive"))
    )
    (net (code "156") (name "unconnected-(M1-GPIO3_B7{slash}MAC_CRS{slash}UART3_TX_(3.3)-Pad193)") (class "Default")
      (node (ref "M1") (pin "193") (pinfunction "GPIO3_B7/MAC_CRS/UART3_TX_(3.3)_193") (pintype "passive"))
    )
    (net (code "157") (name "unconnected-(M1-GPIO3_C0{slash}MAC_COL{slash}UART3_CTSn{slash}SPDIF_TX_(3.3)-Pad190)") (class "Default")
      (node (ref "M1") (pin "190") (pinfunction "GPIO3_C0/MAC_COL/UART3_CTSn/SPDIF_TX_(3.3)_190") (pintype "passive"))
    )
    (net (code "158") (name "unconnected-(M1-GPIO3_C1{slash}MAC_TXCLK{slash}UART3_RTSn_(3.3)-Pad191)") (class "Default")
      (node (ref "M1") (pin "191") (pinfunction "GPIO3_C1/MAC_TXCLK/UART3_RTSn_(3.3)_191") (pintype "passive"))
    )
    (net (code "159") (name "unconnected-(M1-GPIO3_D5{slash}I2S0_SDO2_(1.8)-Pad16)") (class "Default")
      (node (ref "M1") (pin "16") (pinfunction "GPIO3_D5/I2S0_SDO2_(1.8)_16") (pintype "passive"))
    )
    (net (code "160") (name "unconnected-(M1-GPIO4_C5{slash}SPDIF_TX_(3.0)-Pad43)") (class "Default")
      (node (ref "M1") (pin "43") (pinfunction "GPIO4_C5/SPDIF_TX_(3.0)_43") (pintype "passive"))
    )
    (net (code "161") (name "unconnected-(M1-GPIO4_C6{slash}PWM1_(3.0)-Pad33)") (class "Default")
      (node (ref "M1") (pin "33") (pinfunction "GPIO4_C6/PWM1_(3.0)_33") (pintype "passive"))
    )
    (net (code "162") (name "unconnected-(M1-GPIO4_C7{slash}HDMI_CEC_(3.0)-Pad48)") (class "Default")
      (node (ref "M1") (pin "48") (pinfunction "GPIO4_C7/HDMI_CEC_(3.0)_48") (pintype "passive"))
    )
    (net (code "163") (name "unconnected-(M1-GPIO4_D0_(3.0)-Pad145)") (class "Default")
      (node (ref "M1") (pin "145") (pinfunction "GPIO4_D0_(3.0)_145") (pintype "passive"))
    )
    (net (code "164") (name "unconnected-(M1-MIPI_CAMERA_RST#__(1.8)-Pad36)") (class "Default")
      (node (ref "M1") (pin "36") (pinfunction "MIPI_CAMERA_RST#__(1.8)_36") (pintype "passive"))
    )
    (net (code "165") (name "unconnected-(M1-MIPI_RX0_CLKN-Pad68)") (class "Default")
      (node (ref "M1") (pin "68") (pinfunction "MIPI_RX0_CLKN_68") (pintype "passive"))
    )
    (net (code "166") (name "unconnected-(M1-MIPI_RX0_CLKP-Pad69)") (class "Default")
      (node (ref "M1") (pin "69") (pinfunction "MIPI_RX0_CLKP_69") (pintype "passive"))
    )
    (net (code "167") (name "unconnected-(M1-MIPI_RX0_D0N-Pad72)") (class "Default")
      (node (ref "M1") (pin "72") (pinfunction "MIPI_RX0_D0N_72") (pintype "passive"))
    )
    (net (code "168") (name "unconnected-(M1-MIPI_RX0_D0P-Pad73)") (class "Default")
      (node (ref "M1") (pin "73") (pinfunction "MIPI_RX0_D0P_73") (pintype "passive"))
    )
    (net (code "169") (name "unconnected-(M1-MIPI_RX0_D1N-Pad70)") (class "Default")
      (node (ref "M1") (pin "70") (pinfunction "MIPI_RX0_D1N_70") (pintype "passive"))
    )
    (net (code "170") (name "unconnected-(M1-MIPI_RX0_D1P-Pad71)") (class "Default")
      (node (ref "M1") (pin "71") (pinfunction "MIPI_RX0_D1P_71") (pintype "passive"))
    )
    (net (code "171") (name "unconnected-(M1-MIPI_RX0_D2N-Pad66)") (class "Default")
      (node (ref "M1") (pin "66") (pinfunction "MIPI_RX0_D2N_66") (pintype "passive"))
    )
    (net (code "172") (name "unconnected-(M1-MIPI_RX0_D2P-Pad67)") (class "Default")
      (node (ref "M1") (pin "67") (pinfunction "MIPI_RX0_D2P_67") (pintype "passive"))
    )
    (net (code "173") (name "unconnected-(M1-MIPI_RX0_D3N-Pad64)") (class "Default")
      (node (ref "M1") (pin "64") (pinfunction "MIPI_RX0_D3N_64") (pintype "passive"))
    )
    (net (code "174") (name "unconnected-(M1-MIPI_RX0_D3P-Pad65)") (class "Default")
      (node (ref "M1") (pin "65") (pinfunction "MIPI_RX0_D3P_65") (pintype "passive"))
    )
    (net (code "175") (name "unconnected-(M1-MIPI_TX1{slash}RX1_CLKN-Pad58)") (class "Default")
      (node (ref "M1") (pin "58") (pinfunction "MIPI_TX1/RX1_CLKN_58") (pintype "passive"))
    )
    (net (code "176") (name "unconnected-(M1-MIPI_TX1{slash}RX1_CLKP-Pad59)") (class "Default")
      (node (ref "M1") (pin "59") (pinfunction "MIPI_TX1/RX1_CLKP_59") (pintype "passive"))
    )
    (net (code "177") (name "unconnected-(M1-MIPI_TX1{slash}RX1_D0N-Pad54)") (class "Default")
      (node (ref "M1") (pin "54") (pinfunction "MIPI_TX1/RX1_D0N_54") (pintype "passive"))
    )
    (net (code "178") (name "unconnected-(M1-MIPI_TX1{slash}RX1_D0P-Pad55)") (class "Default")
      (node (ref "M1") (pin "55") (pinfunction "MIPI_TX1/RX1_D0P_55") (pintype "passive"))
    )
    (net (code "179") (name "unconnected-(M1-MIPI_TX1{slash}RX1_D1N-Pad56)") (class "Default")
      (node (ref "M1") (pin "56") (pinfunction "MIPI_TX1/RX1_D1N_56") (pintype "passive"))
    )
    (net (code "180") (name "unconnected-(M1-MIPI_TX1{slash}RX1_D1P-Pad57)") (class "Default")
      (node (ref "M1") (pin "57") (pinfunction "MIPI_TX1/RX1_D1P_57") (pintype "passive"))
    )
    (net (code "181") (name "unconnected-(M1-MIPI_TX1{slash}RX1_D2N-Pad60)") (class "Default")
      (node (ref "M1") (pin "60") (pinfunction "MIPI_TX1/RX1_D2N_60") (pintype "passive"))
    )
    (net (code "182") (name "unconnected-(M1-MIPI_TX1{slash}RX1_D2P-Pad61)") (class "Default")
      (node (ref "M1") (pin "61") (pinfunction "MIPI_TX1/RX1_D2P_61") (pintype "passive"))
    )
    (net (code "183") (name "unconnected-(M1-MIPI_TX1{slash}RX1_D3N-Pad62)") (class "Default")
      (node (ref "M1") (pin "62") (pinfunction "MIPI_TX1/RX1_D3N_62") (pintype "passive"))
    )
    (net (code "184") (name "unconnected-(M1-MIPI_TX1{slash}RX1_D3P-Pad63)") (class "Default")
      (node (ref "M1") (pin "63") (pinfunction "MIPI_TX1/RX1_D3P_63") (pintype "passive"))
    )
    (net (code "185") (name "unconnected-(M1-TYPEC0_RX1N-Pad97)") (class "Default")
      (node (ref "M1") (pin "97") (pinfunction "TYPEC0_RX1N_97") (pintype "passive"))
    )
    (net (code "186") (name "unconnected-(M1-TYPEC0_RX1P-Pad98)") (class "Default")
      (node (ref "M1") (pin "98") (pinfunction "TYPEC0_RX1P_98") (pintype "passive"))
    )
    (net (code "187") (name "unconnected-(M1-TYPEC0_RX2N-Pad101)") (class "Default")
      (node (ref "M1") (pin "101") (pinfunction "TYPEC0_RX2N_101") (pintype "passive"))
    )
    (net (code "188") (name "unconnected-(M1-TYPEC0_RX2N-Pad102)") (class "Default")
      (node (ref "M1") (pin "102") (pinfunction "TYPEC0_RX2N_102") (pintype "passive"))
    )
    (net (code "189") (name "unconnected-(M1-TYPEC0_TX1N-Pad100)") (class "Default")
      (node (ref "M1") (pin "100") (pinfunction "TYPEC0_TX1N_100") (pintype "passive"))
    )
    (net (code "190") (name "unconnected-(M1-TYPEC0_TX1P-Pad99)") (class "Default")
      (node (ref "M1") (pin "99") (pinfunction "TYPEC0_TX1P_99") (pintype "passive"))
    )
    (net (code "191") (name "unconnected-(M1-TYPEC0_TX2N-Pad104)") (class "Default")
      (node (ref "M1") (pin "104") (pinfunction "TYPEC0_TX2N_104") (pintype "passive"))
    )
    (net (code "192") (name "unconnected-(M1-TYPEC0_TX2P-Pad103)") (class "Default")
      (node (ref "M1") (pin "103") (pinfunction "TYPEC0_TX2P_103") (pintype "passive"))
    )
    (net (code "193") (name "unconnected-(M1-USB3_DM-Pad114)") (class "Default")
      (node (ref "M1") (pin "114") (pinfunction "USB3_DM_114") (pintype "passive"))
    )
    (net (code "194") (name "unconnected-(M1-USB3_DP-Pad115)") (class "Default")
      (node (ref "M1") (pin "115") (pinfunction "USB3_DP_115") (pintype "passive"))
    )
    (net (code "195") (name "unconnected-(M1-USB3_SSRXN-Pad110)") (class "Default")
      (node (ref "M1") (pin "110") (pinfunction "USB3_SSRXN_110") (pintype "passive"))
    )
    (net (code "196") (name "unconnected-(M1-USB3_SSRXP-Pad109)") (class "Default")
      (node (ref "M1") (pin "109") (pinfunction "USB3_SSRXP_109") (pintype "passive"))
    )
    (net (code "197") (name "unconnected-(M1-USB3_SSTXN-Pad108)") (class "Default")
      (node (ref "M1") (pin "108") (pinfunction "USB3_SSTXN_108") (pintype "passive"))
    )
    (net (code "198") (name "unconnected-(M1-USB3_SSTXP-Pad107)") (class "Default")
      (node (ref "M1") (pin "107") (pinfunction "USB3_SSTXP_107") (pintype "passive"))
    )
  )
)
